# RF_Communication_Board.net
KiCad netlist of a schematic drawn in Altium Designer
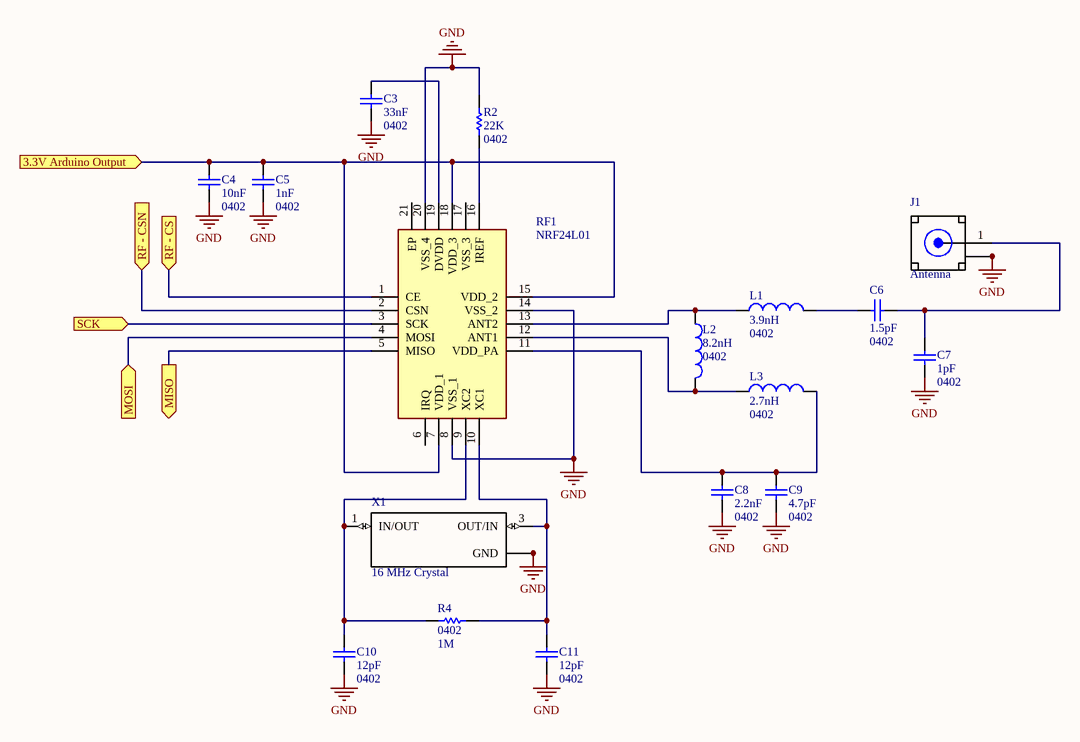
[diagram p0: RF Communication Board.SchDoc]

(export (version "E")
  (design (tool "Eeschema 10.0.6"))
  (components
    (comp (ref "C3")
      (value "33nF")
      (footprint "SMD-0402C")
      (description "Capacitor")
      (fields (field (name "ALTIUM_VALUE") "0402") (field (name "PUBLISHER") "Altium Limited"))
      (libsource (lib "Miscellaneous Devices") (part "Cap"))
    )
    (comp (ref "C4")
      (value "10nF")
      (footprint "SMD-0402C")
      (description "Capacitor")
      (fields (field (name "ALTIUM_VALUE") "0402") (field (name "PUBLISHER") "Altium Limited"))
      (libsource (lib "Miscellaneous Devices") (part "Cap"))
    )
    (comp (ref "C5")
      (value "1nF")
      (footprint "SMD-0402C")
      (description "Capacitor")
      (fields (field (name "ALTIUM_VALUE") "0402") (field (name "PUBLISHER") "Altium Limited"))
      (libsource (lib "Miscellaneous Devices") (part "Cap"))
    )
    (comp (ref "C6")
      (value "1.5pF")
      (footprint "SMD-0402C")
      (description "Capacitor")
      (fields (field (name "ALTIUM_VALUE") "0402") (field (name "PUBLISHER") "Altium Limited"))
      (libsource (lib "Miscellaneous Devices") (part "Cap"))
    )
    (comp (ref "C7")
      (value "1pF")
      (footprint "SMD-0402C")
      (description "Capacitor")
      (fields (field (name "ALTIUM_VALUE") "0402") (field (name "PUBLISHER") "Altium Limited"))
      (libsource (lib "Miscellaneous Devices") (part "Cap"))
    )
    (comp (ref "C8")
      (value "2.2nF")
      (footprint "SMD-0402C")
      (description "Capacitor")
      (fields (field (name "ALTIUM_VALUE") "0402") (field (name "PUBLISHER") "Altium Limited"))
      (libsource (lib "Miscellaneous Devices") (part "Cap"))
    )
    (comp (ref "C9")
      (value "4.7pF")
      (footprint "SMD-0402C")
      (description "Capacitor")
      (fields (field (name "ALTIUM_VALUE") "0402") (field (name "PUBLISHER") "Altium Limited"))
      (libsource (lib "Miscellaneous Devices") (part "Cap"))
    )
    (comp (ref "C10")
      (value "12pF")
      (footprint "SMD-0402C")
      (description "Capacitor")
      (fields (field (name "ALTIUM_VALUE") "0402") (field (name "PUBLISHER") "Altium Limited"))
      (libsource (lib "Miscellaneous Devices") (part "Cap"))
    )
    (comp (ref "C11")
      (value "12pF")
      (footprint "SMD-0402C")
      (description "Capacitor")
      (fields (field (name "ALTIUM_VALUE") "0402") (field (name "PUBLISHER") "Altium Limited"))
      (libsource (lib "Miscellaneous Devices") (part "Cap"))
    )
    (comp (ref "J1")
      (value "Antenna")
      (footprint "*SAMTEC_SMA-J-P-H-RA-TH1")
      (description "SMA Connector Jack, Female Socket 50Ohm Through Hole, Right Angle Solder")
      (fields (field (name "MP") "SMA-J-P-H-RA-TH1") (field (name "MF") "Samtec"))
      (libsource (lib "SMA-J-P-H-RA-TH1") (part "SMA-J-P-H-RA-TH1"))
    )
    (comp (ref "L1")
      (value "3.9nH")
      (footprint "0402-A")
      (description "Inductor")
      (fields (field (name "ALTIUM_VALUE") "0402") (field (name "PUBLISHER") "Altium Limited"))
      (libsource (lib "Miscellaneous Devices") (part "Inductor"))
    )
    (comp (ref "L2")
      (value "8.2nH")
      (footprint "0402-A")
      (description "Inductor")
      (fields (field (name "ALTIUM_VALUE") "0402") (field (name "PUBLISHER") "Altium Limited"))
      (libsource (lib "Miscellaneous Devices") (part "Inductor"))
    )
    (comp (ref "L3")
      (value "2.7nH")
      (footprint "0402-A")
      (description "Inductor")
      (fields (field (name "ALTIUM_VALUE") "0402") (field (name "PUBLISHER") "Altium Limited"))
      (libsource (lib "Miscellaneous Devices") (part "Inductor"))
    )
    (comp (ref "R2")
      (value "22K")
      (footprint "SMD-0402-RES")
      (description "Resistor")
      (fields (field (name "ALTIUM_VALUE") "0402") (field (name "PUBLISHER") "Altium Limited"))
      (libsource (lib "Miscellaneous Devices") (part "Res1"))
    )
    (comp (ref "R4")
      (value "0402")
      (footprint "SMD-0402-RES")
      (description "Resistor")
      (fields (field (name "ALTIUM_VALUE") "1M") (field (name "PUBLISHER") "Altium Limited"))
      (libsource (lib "Miscellaneous Devices") (part "Res1"))
    )
    (comp (ref "RF1")
      (value "NRF24L01")
      (footprint "QFN50P400X400X95-21N-D")
      (description "Integrated Circuit")
      (fields (field (name "MOUSER PART NUMBER") "949-NRF24L01") (field (name "RS PART NUMBER") "6156531"))
      (libsource (lib "*") (part "NRF24L01"))
    )
    (comp (ref "X1")
      (value "16 MHz Crystal")
      (footprint "*XTAL_ECS-160-12-30BQ-AEN-TR")
      (description "16MHz Â±25ppm Crystal 12pF 50 Ohms 4-SMD, No Lead")
      (fields (field (name "MP") "ECS-160-12-30BQ-AEN-TR") (field (name "MF") "ECS Inc."))
      (libsource (lib "ECS-160-12-30BQ-AEN-TR") (part "ECS-160-12-30BQ-AEN-TR"))
    )
  )
  (nets
    (net (code "1") (name "/3.3V Arduino Output") (class "Default")
      (node (ref "C4") (pin "2") (pinfunction "2_2") (pintype "passive"))
      (node (ref "C5") (pin "2") (pinfunction "2_2") (pintype "passive"))
      (node (ref "RF1") (pin "15") (pinfunction "VDD_2_15") (pintype "passive"))
      (node (ref "RF1") (pin "18") (pinfunction "VDD_3_18") (pintype "passive"))
      (node (ref "RF1") (pin "7") (pinfunction "VDD_1_7") (pintype "passive"))
    )
    (net (code "2") (name "/MISO") (class "Default")
      (node (ref "RF1") (pin "5") (pinfunction "MISO_5") (pintype "passive"))
    )
    (net (code "3") (name "/MOSI") (class "Default")
      (node (ref "RF1") (pin "4") (pinfunction "MOSI_4") (pintype "passive"))
    )
    (net (code "4") (name "/RF - CS") (class "Default")
      (node (ref "RF1") (pin "1") (pinfunction "CE_1") (pintype "passive"))
    )
    (net (code "5") (name "/RF - CSN") (class "Default")
      (node (ref "RF1") (pin "2") (pinfunction "CSN_2") (pintype "passive"))
    )
    (net (code "6") (name "/SCK") (class "Default")
      (node (ref "RF1") (pin "3") (pinfunction "SCK_3") (pintype "passive"))
    )
    (net (code "7") (name "GND") (class "Default")
      (node (ref "C10") (pin "1") (pinfunction "1_1") (pintype "passive"))
      (node (ref "C11") (pin "1") (pinfunction "1_1") (pintype "passive"))
      (node (ref "C3") (pin "1") (pinfunction "1_1") (pintype "passive"))
      (node (ref "C4") (pin "1") (pinfunction "1_1") (pintype "passive"))
      (node (ref "C5") (pin "1") (pinfunction "1_1") (pintype "passive"))
      (node (ref "C7") (pin "1") (pinfunction "1_1") (pintype "passive"))
      (node (ref "C8") (pin "1") (pinfunction "1_1") (pintype "passive"))
      (node (ref "C9") (pin "1") (pinfunction "1_1") (pintype "passive"))
      (node (ref "J1") (pin "2") (pinfunction "GND_2") (pintype "power_in"))
      (node (ref "J1") (pin "3") (pinfunction "GND_3") (pintype "power_in"))
      (node (ref "J1") (pin "4") (pinfunction "GND_4") (pintype "power_in"))
      (node (ref "J1") (pin "5") (pinfunction "GND_5") (pintype "power_in"))
      (node (ref "R2") (pin "2") (pinfunction "2_2") (pintype "passive"))
      (node (ref "RF1") (pin "14") (pinfunction "VSS_2_14") (pintype "passive"))
      (node (ref "RF1") (pin "20") (pinfunction "VSS_4_20") (pintype "passive"))
      (node (ref "RF1") (pin "8") (pinfunction "VSS_1_8") (pintype "passive"))
      (node (ref "X1") (pin "2") (pinfunction "GND_2") (pintype "power_in"))
      (node (ref "X1") (pin "4") (pinfunction "GND_4") (pintype "power_in"))
    )
    (net (code "8") (name "Net-(C6-Pad1)") (class "Default")
      (node (ref "C6") (pin "1") (pinfunction "1_1") (pintype "passive"))
      (node (ref "L1") (pin "2") (pinfunction "2_2") (pintype "passive"))
    )
    (net (code "9") (name "Net-(J1-SIGNAL)") (class "Default")
      (node (ref "C6") (pin "2") (pinfunction "2_2") (pintype "passive"))
      (node (ref "C7") (pin "2") (pinfunction "2_2") (pintype "passive"))
      (node (ref "J1") (pin "1") (pinfunction "SIGNAL_1") (pintype "passive"))
    )
    (net (code "10") (name "Net-(RF1-ANT1)") (class "Default")
      (node (ref "L2") (pin "2") (pinfunction "2_2") (pintype "passive"))
      (node (ref "L3") (pin "1") (pinfunction "1_1") (pintype "passive"))
      (node (ref "RF1") (pin "12") (pinfunction "ANT1_12") (pintype "passive"))
    )
    (net (code "11") (name "Net-(RF1-ANT2)") (class "Default")
      (node (ref "L1") (pin "1") (pinfunction "1_1") (pintype "passive"))
      (node (ref "L2") (pin "1") (pinfunction "1_1") (pintype "passive"))
      (node (ref "RF1") (pin "13") (pinfunction "ANT2_13") (pintype "passive"))
    )
    (net (code "12") (name "Net-(RF1-DVDD)") (class "Default")
      (node (ref "C3") (pin "2") (pinfunction "2_2") (pintype "passive"))
      (node (ref "RF1") (pin "19") (pinfunction "DVDD_19") (pintype "passive"))
    )
    (net (code "13") (name "Net-(RF1-IREF)") (class "Default")
      (node (ref "R2") (pin "1") (pinfunction "1_1") (pintype "passive"))
      (node (ref "RF1") (pin "16") (pinfunction "IREF_16") (pintype "passive"))
    )
    (net (code "14") (name "Net-(RF1-VDD_PA)") (class "Default")
      (node (ref "C8") (pin "2") (pinfunction "2_2") (pintype "passive"))
      (node (ref "C9") (pin "2") (pinfunction "2_2") (pintype "passive"))
      (node (ref "L3") (pin "2") (pinfunction "2_2") (pintype "passive"))
      (node (ref "RF1") (pin "11") (pinfunction "VDD_PA_11") (pintype "passive"))
    )
    (net (code "15") (name "Net-(RF1-XC1)") (class "Default")
      (node (ref "C11") (pin "2") (pinfunction "2_2") (pintype "passive"))
      (node (ref "R4") (pin "1") (pinfunction "1_1") (pintype "passive"))
      (node (ref "RF1") (pin "10") (pinfunction "XC1_10") (pintype "passive"))
      (node (ref "X1") (pin "3") (pinfunction "OUT/IN_3") (pintype "bidirectional"))
    )
    (net (code "16") (name "Net-(RF1-XC2)") (class "Default")
      (node (ref "C10") (pin "2") (pinfunction "2_2") (pintype "passive"))
      (node (ref "R4") (pin "2") (pinfunction "2_2") (pintype "passive"))
      (node (ref "RF1") (pin "9") (pinfunction "XC2_9") (pintype "passive"))
      (node (ref "X1") (pin "1") (pinfunction "IN/OUT_1") (pintype "bidirectional"))
    )
    (net (code "17") (name "unconnected-(RF1-EP-Pad21)") (class "Default")
      (node (ref "RF1") (pin "21") (pinfunction "EP_21") (pintype "passive"))
    )
    (net (code "18") (name "unconnected-(RF1-IRQ-Pad6)") (class "Default")
      (node (ref "RF1") (pin "6") (pinfunction "IRQ_6") (pintype "passive"))
    )
    (net (code "19") (name "unconnected-(RF1-VSS_3-Pad17)") (class "Default")
      (node (ref "RF1") (pin "17") (pinfunction "VSS_3_17") (pintype "passive"))
    )
  )
)
